# aquaUI.net
KiCad netlist of a schematic drawn in EAGLE
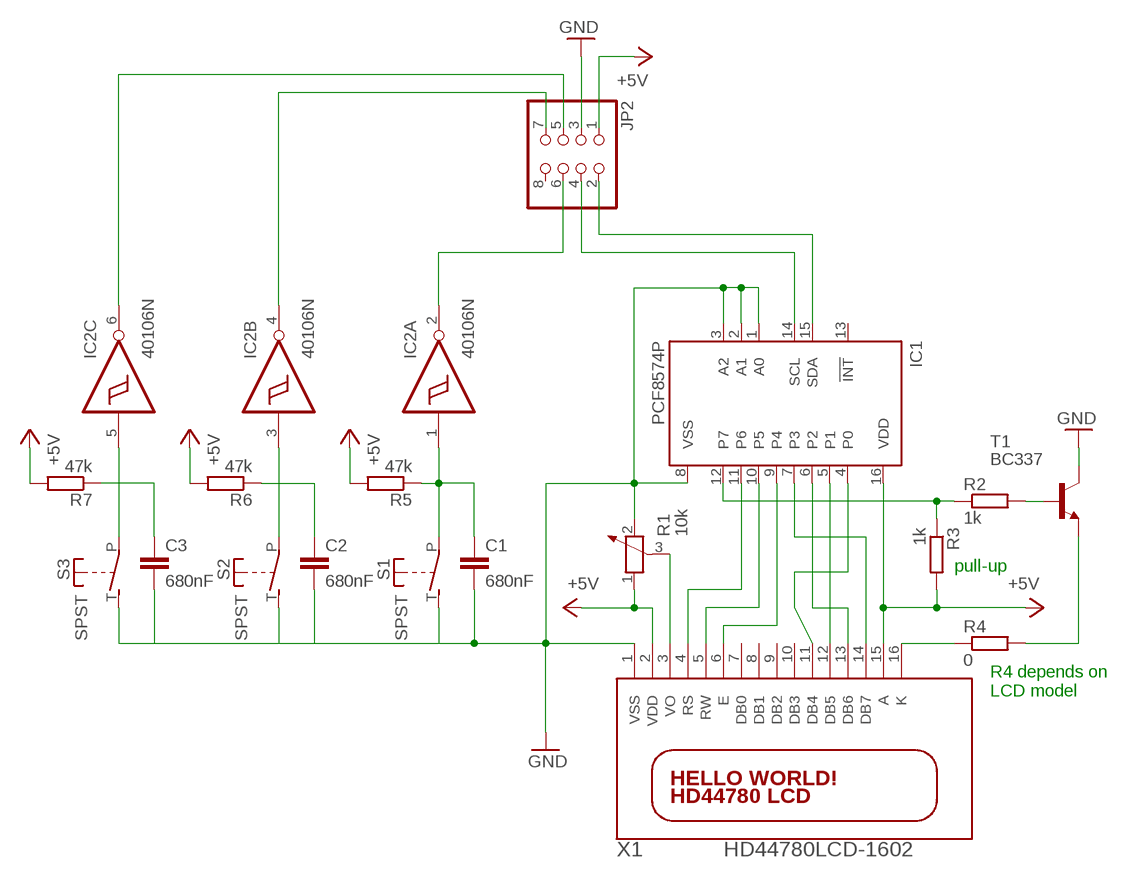
[diagram p0: schematic, sheet 1]

(export (version "E")
  (design (tool "Eeschema 10.0.6"))
  (components
    (comp (ref "C1")
      (value "680nF")
      (footprint "eagle-import:C050-050X075")
      (libsource (lib "eagle-import") (part "C-EU050-050X075"))
    )
    (comp (ref "C2")
      (value "680nF")
      (footprint "eagle-import:C050-050X075")
      (libsource (lib "eagle-import") (part "C-EU050-050X075"))
    )
    (comp (ref "C3")
      (value "680nF")
      (footprint "eagle-import:C050-050X075")
      (libsource (lib "eagle-import") (part "C-EU050-050X075"))
    )
    (comp (ref "IC1")
      (value "PCF8574P")
      (footprint "eagle-import:DIL16")
      (fields (field (name "MPN") "PCF8574PN"))
      (libsource (lib "eagle-import") (part "PCF8574P"))
    )
    (comp (ref "IC2")
      (value "40106N")
      (footprint "eagle-import:DIL14")
      (libsource (lib "eagle-import") (part "40106N"))
    )
    (comp (ref "JP2")
      (value "PINHD-2X4")
      (footprint "eagle-import:2X04")
      (libsource (lib "eagle-import") (part "PINHD-2X4"))
    )
    (comp (ref "R1")
      (value "10k")
      (footprint "eagle-import:PT-10")
      (libsource (lib "eagle-import") (part "POTENTIOMETER_PT-10"))
    )
    (comp (ref "R2")
      (value "1k")
      (footprint "eagle-import:0204_5")
      (libsource (lib "eagle-import") (part "R-EU_0204/5"))
    )
    (comp (ref "R3")
      (value "1k")
      (footprint "eagle-import:0204_5")
      (libsource (lib "eagle-import") (part "R-EU_0204/5"))
    )
    (comp (ref "R4")
      (value "0")
      (footprint "eagle-import:0204_5")
      (libsource (lib "eagle-import") (part "R-EU_0204/5"))
    )
    (comp (ref "R5")
      (value "47k")
      (footprint "eagle-import:0204_5")
      (libsource (lib "eagle-import") (part "R-EU_0204/5"))
    )
    (comp (ref "R6")
      (value "47k")
      (footprint "eagle-import:0204_5")
      (libsource (lib "eagle-import") (part "R-EU_0204/5"))
    )
    (comp (ref "R7")
      (value "47k")
      (footprint "eagle-import:0204_5")
      (libsource (lib "eagle-import") (part "R-EU_0204/5"))
    )
    (comp (ref "S1")
      (value "SPST")
      (footprint "eagle-import:JUDCOSPST")
      (libsource (lib "eagle-import") (part "SPST"))
    )
    (comp (ref "S2")
      (value "SPST")
      (footprint "eagle-import:JUDCOSPST")
      (libsource (lib "eagle-import") (part "SPST"))
    )
    (comp (ref "S3")
      (value "SPST")
      (footprint "eagle-import:JUDCOSPST")
      (libsource (lib "eagle-import") (part "SPST"))
    )
    (comp (ref "T1")
      (value "BC337")
      (footprint "eagle-import:TO92")
      (libsource (lib "eagle-import") (part "BC337"))
    )
    (comp (ref "X1")
      (value "HD44780LCD-1602")
      (footprint "eagle-import:LCD1602")
      (libsource (lib "eagle-import") (part "HD44780LCD-1602"))
    )
  )
  (nets
    (net (code "1") (name "+5V") (class "Default")
      (node (ref "IC1") (pin "16") (pinfunction "VDD_16") (pintype "power_in"))
      (node (ref "JP2") (pin "1") (pinfunction "1_1") (pintype "passive"))
      (node (ref "R1") (pin "1") (pinfunction "1_1") (pintype "passive"))
      (node (ref "R3") (pin "2") (pinfunction "2_2") (pintype "passive"))
      (node (ref "R5") (pin "2") (pinfunction "2_2") (pintype "passive"))
      (node (ref "R6") (pin "2") (pinfunction "2_2") (pintype "passive"))
      (node (ref "R7") (pin "2") (pinfunction "2_2") (pintype "passive"))
      (node (ref "X1") (pin "15") (pinfunction "A_15") (pintype "input"))
      (node (ref "X1") (pin "2") (pinfunction "VDD_2") (pintype "power_in"))
    )
    (net (code "2") (name "GND") (class "Default")
      (node (ref "C1") (pin "2") (pinfunction "2_2") (pintype "passive"))
      (node (ref "C2") (pin "2") (pinfunction "2_2") (pintype "passive"))
      (node (ref "C3") (pin "2") (pinfunction "2_2") (pintype "passive"))
      (node (ref "IC1") (pin "1") (pinfunction "A0_1") (pintype "input"))
      (node (ref "IC1") (pin "2") (pinfunction "A1_2") (pintype "input"))
      (node (ref "IC1") (pin "3") (pinfunction "A2_3") (pintype "input"))
      (node (ref "IC1") (pin "8") (pinfunction "VSS_8") (pintype "power_in"))
      (node (ref "JP2") (pin "3") (pinfunction "3_3") (pintype "passive"))
      (node (ref "R1") (pin "2") (pinfunction "2_2") (pintype "passive"))
      (node (ref "S1") (pin "T") (pinfunction "S_T") (pintype "passive"))
      (node (ref "S2") (pin "T") (pinfunction "S_T") (pintype "passive"))
      (node (ref "S3") (pin "T") (pinfunction "S_T") (pintype "passive"))
      (node (ref "T1") (pin "3") (pinfunction "C_3") (pintype "passive"))
      (node (ref "X1") (pin "1") (pinfunction "VSS_1") (pintype "power_in"))
    )
    (net (code "3") (name "Net-(IC1-P0)") (class "Default")
      (node (ref "IC1") (pin "4") (pinfunction "P0_4") (pintype "bidirectional"))
      (node (ref "X1") (pin "11") (pinfunction "DB4_11") (pintype "bidirectional"))
    )
    (net (code "4") (name "Net-(IC1-P1)") (class "Default")
      (node (ref "IC1") (pin "5") (pinfunction "P1_5") (pintype "bidirectional"))
      (node (ref "X1") (pin "12") (pinfunction "DB5_12") (pintype "bidirectional"))
    )
    (net (code "5") (name "Net-(IC1-P2)") (class "Default")
      (node (ref "IC1") (pin "6") (pinfunction "P2_6") (pintype "bidirectional"))
      (node (ref "X1") (pin "13") (pinfunction "DB6_13") (pintype "bidirectional"))
    )
    (net (code "6") (name "Net-(IC1-P3)") (class "Default")
      (node (ref "IC1") (pin "7") (pinfunction "P3_7") (pintype "bidirectional"))
      (node (ref "X1") (pin "14") (pinfunction "DB7_14") (pintype "bidirectional"))
    )
    (net (code "7") (name "Net-(IC1-P4)") (class "Default")
      (node (ref "IC1") (pin "9") (pinfunction "P4_9") (pintype "bidirectional"))
      (node (ref "X1") (pin "6") (pinfunction "E_6") (pintype "input"))
    )
    (net (code "8") (name "Net-(IC1-P5)") (class "Default")
      (node (ref "IC1") (pin "10") (pinfunction "P5_10") (pintype "bidirectional"))
      (node (ref "X1") (pin "5") (pinfunction "RW_5") (pintype "input"))
    )
    (net (code "9") (name "Net-(IC1-P6)") (class "Default")
      (node (ref "IC1") (pin "11") (pinfunction "P6_11") (pintype "bidirectional"))
      (node (ref "X1") (pin "4") (pinfunction "RS_4") (pintype "input"))
    )
    (net (code "10") (name "Net-(IC1-P7)") (class "Default")
      (node (ref "IC1") (pin "12") (pinfunction "P7_12") (pintype "bidirectional"))
      (node (ref "R2") (pin "1") (pinfunction "1_1") (pintype "passive"))
      (node (ref "R3") (pin "1") (pinfunction "1_1") (pintype "passive"))
    )
    (net (code "11") (name "Net-(IC1-SCL)") (class "Default")
      (node (ref "IC1") (pin "14") (pinfunction "SCL_14") (pintype "input"))
      (node (ref "JP2") (pin "4") (pinfunction "4_4") (pintype "passive"))
    )
    (net (code "12") (name "Net-(IC1-SDA)") (class "Default")
      (node (ref "IC1") (pin "15") (pinfunction "SDA_15") (pintype "bidirectional"))
      (node (ref "JP2") (pin "2") (pinfunction "2_2") (pintype "passive"))
    )
    (net (code "13") (name "Net-(IC2A-I)") (class "Default")
      (node (ref "C1") (pin "1") (pinfunction "1_1") (pintype "passive"))
      (node (ref "IC2") (pin "1") (pinfunction "I_1") (pintype "input"))
      (node (ref "R5") (pin "1") (pinfunction "1_1") (pintype "passive"))
      (node (ref "S1") (pin "P") (pinfunction "P_P") (pintype "passive"))
    )
    (net (code "14") (name "Net-(IC2A-O)") (class "Default")
      (node (ref "IC2") (pin "2") (pinfunction "O_2") (pintype "output"))
      (node (ref "JP2") (pin "6") (pinfunction "6_6") (pintype "passive"))
    )
    (net (code "15") (name "Net-(IC2B-I)") (class "Default")
      (node (ref "C2") (pin "1") (pinfunction "1_1") (pintype "passive"))
      (node (ref "IC2") (pin "3") (pinfunction "I_3") (pintype "input"))
      (node (ref "R6") (pin "1") (pinfunction "1_1") (pintype "passive"))
      (node (ref "S2") (pin "P") (pinfunction "P_P") (pintype "passive"))
    )
    (net (code "16") (name "Net-(IC2B-O)") (class "Default")
      (node (ref "IC2") (pin "4") (pinfunction "O_4") (pintype "output"))
      (node (ref "JP2") (pin "7") (pinfunction "7_7") (pintype "passive"))
    )
    (net (code "17") (name "Net-(IC2C-I)") (class "Default")
      (node (ref "C3") (pin "1") (pinfunction "1_1") (pintype "passive"))
      (node (ref "IC2") (pin "5") (pinfunction "I_5") (pintype "input"))
      (node (ref "R7") (pin "1") (pinfunction "1_1") (pintype "passive"))
      (node (ref "S3") (pin "P") (pinfunction "P_P") (pintype "passive"))
    )
    (net (code "18") (name "Net-(IC2C-O)") (class "Default")
      (node (ref "IC2") (pin "6") (pinfunction "O_6") (pintype "output"))
      (node (ref "JP2") (pin "5") (pinfunction "5_5") (pintype "passive"))
    )
    (net (code "19") (name "Net-(T1-B)") (class "Default")
      (node (ref "R2") (pin "2") (pinfunction "2_2") (pintype "passive"))
      (node (ref "T1") (pin "2") (pinfunction "B_2") (pintype "passive"))
    )
    (net (code "20") (name "Net-(T1-E)") (class "Default")
      (node (ref "R4") (pin "2") (pinfunction "2_2") (pintype "passive"))
      (node (ref "T1") (pin "1") (pinfunction "E_1") (pintype "passive"))
    )
    (net (code "21") (name "Net-(X1-K)") (class "Default")
      (node (ref "R4") (pin "1") (pinfunction "1_1") (pintype "passive"))
      (node (ref "X1") (pin "16") (pinfunction "K_16") (pintype "input"))
    )
    (net (code "22") (name "Net-(X1-VO)") (class "Default")
      (node (ref "R1") (pin "3") (pinfunction "3_3") (pintype "passive"))
      (node (ref "X1") (pin "3") (pinfunction "VO_3") (pintype "input"))
    )
    (net (code "23") (name "unconnected-(IC1-~{INT}-Pad13)") (class "Default")
      (node (ref "IC1") (pin "13") (pinfunction "~{INT}_13") (pintype "output"))
    )
    (net (code "24") (name "unconnected-(JP2-Pad8)") (class "Default")
      (node (ref "JP2") (pin "8") (pinfunction "8_8") (pintype "passive"))
    )
    (net (code "25") (name "unconnected-(X1-DB0-Pad7)") (class "Default")
      (node (ref "X1") (pin "7") (pinfunction "DB0_7") (pintype "bidirectional"))
    )
    (net (code "26") (name "unconnected-(X1-DB1-Pad8)") (class "Default")
      (node (ref "X1") (pin "8") (pinfunction "DB1_8") (pintype "bidirectional"))
    )
    (net (code "27") (name "unconnected-(X1-DB2-Pad9)") (class "Default")
      (node (ref "X1") (pin "9") (pinfunction "DB2_9") (pintype "bidirectional"))
    )
    (net (code "28") (name "unconnected-(X1-DB3-Pad10)") (class "Default")
      (node (ref "X1") (pin "10") (pinfunction "DB3_10") (pintype "bidirectional"))
    )
  )
)
